# main.net
KiCad netlist of a schematic drawn in EAGLE
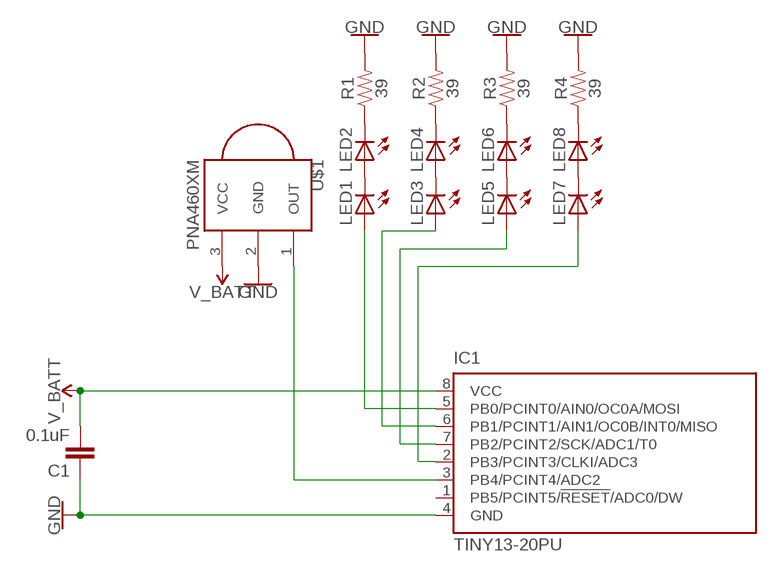
[diagram p0: schematic, sheet 1]

(export (version "E")
  (design (tool "Eeschema 10.0.6"))
  (components
    (comp (ref "C1")
      (value "0.1uF")
      (footprint "eagle-import:CAP-PTH-SMALL-KIT")
      (libsource (lib "eagle-import") (part "0.1UF-KIT-EZ-50V-20%"))
    )
    (comp (ref "IC1")
      (value "TINY13-20PU")
      (footprint "eagle-import:DIL08")
      (fields (field (name "MPN") "ATTINY13-20PU"))
      (libsource (lib "eagle-import") (part "TINY13PU-20"))
    )
    (comp (ref "LED1")
      (value "LED5MM")
      (footprint "eagle-import:LED5MM")
      (libsource (lib "eagle-import") (part "LED5MM"))
    )
    (comp (ref "LED2")
      (value "LED5MM")
      (footprint "eagle-import:LED5MM")
      (libsource (lib "eagle-import") (part "LED5MM"))
    )
    (comp (ref "LED3")
      (value "LED5MM")
      (footprint "eagle-import:LED5MM")
      (libsource (lib "eagle-import") (part "LED5MM"))
    )
    (comp (ref "LED4")
      (value "LED5MM")
      (footprint "eagle-import:LED5MM")
      (libsource (lib "eagle-import") (part "LED5MM"))
    )
    (comp (ref "LED5")
      (value "LED5MM")
      (footprint "eagle-import:LED5MM")
      (libsource (lib "eagle-import") (part "LED5MM"))
    )
    (comp (ref "LED6")
      (value "LED5MM")
      (footprint "eagle-import:LED5MM")
      (libsource (lib "eagle-import") (part "LED5MM"))
    )
    (comp (ref "LED7")
      (value "LED5MM")
      (footprint "eagle-import:LED5MM")
      (libsource (lib "eagle-import") (part "LED5MM"))
    )
    (comp (ref "LED8")
      (value "LED5MM")
      (footprint "eagle-import:LED5MM")
      (libsource (lib "eagle-import") (part "LED5MM"))
    )
    (comp (ref "R1")
      (value "39")
      (footprint "eagle-import:0603")
      (libsource (lib "eagle-import") (part "39KOHM-0603-1/10W-1%"))
    )
    (comp (ref "R2")
      (value "39")
      (footprint "eagle-import:0603")
      (libsource (lib "eagle-import") (part "39KOHM-0603-1/10W-1%"))
    )
    (comp (ref "R3")
      (value "39")
      (footprint "eagle-import:0603")
      (libsource (lib "eagle-import") (part "39KOHM-0603-1/10W-1%"))
    )
    (comp (ref "R4")
      (value "39")
      (footprint "eagle-import:0603")
      (libsource (lib "eagle-import") (part "39KOHM-0603-1/10W-1%"))
    )
    (comp (ref "U$1")
      (value "PNA460XM")
      (footprint "eagle-import:PNA460XM")
      (libsource (lib "eagle-import") (part "PNA460XM"))
    )
  )
  (nets
    (net (code "1") (name "GND") (class "Default")
      (node (ref "C1") (pin "1") (pinfunction "1_1") (pintype "passive"))
      (node (ref "IC1") (pin "4") (pinfunction "GND_4") (pintype "power_in"))
      (node (ref "R1") (pin "2") (pinfunction "2_2") (pintype "passive"))
      (node (ref "R2") (pin "2") (pinfunction "2_2") (pintype "passive"))
      (node (ref "R3") (pin "2") (pinfunction "2_2") (pintype "passive"))
      (node (ref "R4") (pin "2") (pinfunction "2_2") (pintype "passive"))
      (node (ref "U$1") (pin "2") (pinfunction "GND_2") (pintype "power_in"))
    )
    (net (code "2") (name "Net-(IC1-PB0{slash}PCINT0{slash}AIN0{slash}OC0A{slash}MOSI)") (class "Default")
      (node (ref "IC1") (pin "5") (pinfunction "PB0/PCINT0/AIN0/OC0A/MOSI_5") (pintype "bidirectional"))
      (node (ref "LED1") (pin "A") (pinfunction "A_A") (pintype "passive"))
    )
    (net (code "3") (name "Net-(IC1-PB1{slash}PCINT1{slash}AIN1{slash}OC0B{slash}INT0{slash}MISO)") (class "Default")
      (node (ref "IC1") (pin "6") (pinfunction "PB1/PCINT1/AIN1/OC0B/INT0/MISO_6") (pintype "bidirectional"))
      (node (ref "LED3") (pin "A") (pinfunction "A_A") (pintype "passive"))
    )
    (net (code "4") (name "Net-(IC1-PB2{slash}PCINT2{slash}SCK{slash}ADC1{slash}T0)") (class "Default")
      (node (ref "IC1") (pin "7") (pinfunction "PB2/PCINT2/SCK/ADC1/T0_7") (pintype "bidirectional"))
      (node (ref "LED5") (pin "A") (pinfunction "A_A") (pintype "passive"))
    )
    (net (code "5") (name "Net-(IC1-PB3{slash}PCINT3{slash}CLKI{slash}ADC3)") (class "Default")
      (node (ref "IC1") (pin "2") (pinfunction "PB3/PCINT3/CLKI/ADC3_2") (pintype "bidirectional"))
      (node (ref "LED7") (pin "A") (pinfunction "A_A") (pintype "passive"))
    )
    (net (code "6") (name "Net-(IC1-PB4{slash}PCINT4{slash}ADC2)") (class "Default")
      (node (ref "IC1") (pin "3") (pinfunction "PB4/PCINT4/ADC2_3") (pintype "bidirectional"))
      (node (ref "U$1") (pin "1") (pinfunction "OUT_1") (pintype "output"))
    )
    (net (code "7") (name "Net-(LED1-C)") (class "Default")
      (node (ref "LED1") (pin "K") (pinfunction "C_K") (pintype "passive"))
      (node (ref "LED2") (pin "A") (pinfunction "A_A") (pintype "passive"))
    )
    (net (code "8") (name "Net-(LED2-C)") (class "Default")
      (node (ref "LED2") (pin "K") (pinfunction "C_K") (pintype "passive"))
      (node (ref "R1") (pin "1") (pinfunction "1_1") (pintype "passive"))
    )
    (net (code "9") (name "Net-(LED3-C)") (class "Default")
      (node (ref "LED3") (pin "K") (pinfunction "C_K") (pintype "passive"))
      (node (ref "LED4") (pin "A") (pinfunction "A_A") (pintype "passive"))
    )
    (net (code "10") (name "Net-(LED4-C)") (class "Default")
      (node (ref "LED4") (pin "K") (pinfunction "C_K") (pintype "passive"))
      (node (ref "R2") (pin "1") (pinfunction "1_1") (pintype "passive"))
    )
    (net (code "11") (name "Net-(LED5-C)") (class "Default")
      (node (ref "LED5") (pin "K") (pinfunction "C_K") (pintype "passive"))
      (node (ref "LED6") (pin "A") (pinfunction "A_A") (pintype "passive"))
    )
    (net (code "12") (name "Net-(LED6-C)") (class "Default")
      (node (ref "LED6") (pin "K") (pinfunction "C_K") (pintype "passive"))
      (node (ref "R3") (pin "1") (pinfunction "1_1") (pintype "passive"))
    )
    (net (code "13") (name "Net-(LED7-C)") (class "Default")
      (node (ref "LED7") (pin "K") (pinfunction "C_K") (pintype "passive"))
      (node (ref "LED8") (pin "A") (pinfunction "A_A") (pintype "passive"))
    )
    (net (code "14") (name "Net-(LED8-C)") (class "Default")
      (node (ref "LED8") (pin "K") (pinfunction "C_K") (pintype "passive"))
      (node (ref "R4") (pin "1") (pinfunction "1_1") (pintype "passive"))
    )
    (net (code "15") (name "V_BATT") (class "Default")
      (node (ref "C1") (pin "2") (pinfunction "2_2") (pintype "passive"))
      (node (ref "IC1") (pin "8") (pinfunction "VCC_8") (pintype "power_in"))
      (node (ref "U$1") (pin "3") (pinfunction "VCC_3") (pintype "power_in"))
    )
    (net (code "16") (name "unconnected-(IC1-PB5{slash}PCINT5{slash}~{RESET}{slash}ADC0{slash}DW-Pad1)") (class "Default")
      (node (ref "IC1") (pin "1") (pinfunction "PB5/PCINT5/~{RESET}/ADC0/DW_1") (pintype "bidirectional"))
    )
  )
)
